# MineSwipper_Main_controller_USB.net
KiCad netlist of a schematic drawn in EAGLE
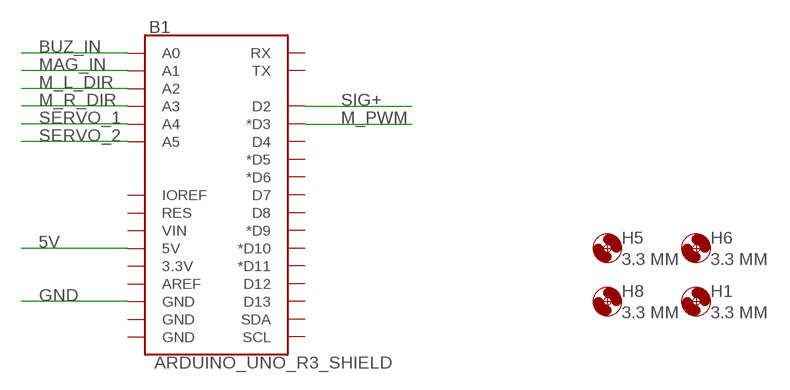
[diagram p0: schematic, sheet 1]
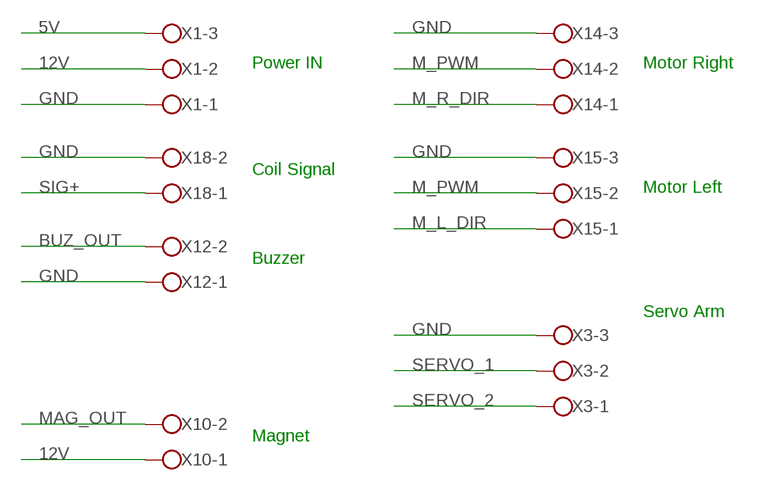
[diagram p1: schematic, sheet 2]
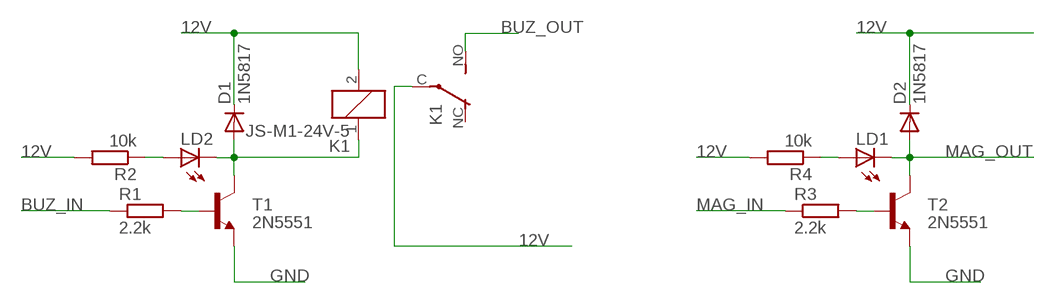
[diagram p2: schematic, sheet 3]

(export (version "E")
  (design (tool "Eeschema 10.0.6"))
  (components
    (comp (ref "D1")
      (value "1N5817")
      (footprint "eagle-import:DO41-10")
      (libsource (lib "eagle-import") (part "1N4004"))
    )
    (comp (ref "D2")
      (value "1N5817")
      (footprint "eagle-import:DO41-10")
      (libsource (lib "eagle-import") (part "1N4004"))
    )
    (comp (ref "K1")
      (value "JS-M1-24V-5")
      (footprint "eagle-import:JS-M")
      (fields (field (name "MF") "FARNELL") (field (name "MPN") "JSM1-12V-5"))
      (libsource (lib "eagle-import") (part "JS-M1-12V-5"))
    )
    (comp (ref "LD1")
      (value "LED5MM")
      (footprint "eagle-import:LED5MM")
      (libsource (lib "eagle-import") (part "LED5MM"))
    )
    (comp (ref "LD2")
      (value "LED5MM")
      (footprint "eagle-import:LED5MM")
      (libsource (lib "eagle-import") (part "LED5MM"))
    )
    (comp (ref "R1")
      (value "2.2k")
      (footprint "eagle-import:0207_10")
      (libsource (lib "eagle-import") (part "R-EU_0207/10"))
    )
    (comp (ref "R2")
      (value "10k")
      (footprint "eagle-import:0207_10")
      (libsource (lib "eagle-import") (part "R-EU_0207/10"))
    )
    (comp (ref "R3")
      (value "2.2k")
      (footprint "eagle-import:0207_10")
      (libsource (lib "eagle-import") (part "R-EU_0207/10"))
    )
    (comp (ref "R4")
      (value "10k")
      (footprint "eagle-import:0207_10")
      (libsource (lib "eagle-import") (part "R-EU_0207/10"))
    )
    (comp (ref "T1")
      (value "2N5551")
      (footprint "eagle-import:TO92-EBC-OVAL")
      (libsource (lib "eagle-import") (part "2N2222"))
    )
    (comp (ref "T2")
      (value "2N5551")
      (footprint "eagle-import:TO92-EBC-OVAL")
      (libsource (lib "eagle-import") (part "2N2222"))
    )
    (comp (ref "X1")
      (value "W237-103")
      (footprint "eagle-import:W237-103")
      (fields (field (name "MPN") "237-103"))
      (libsource (lib "eagle-import") (part "W237-103"))
    )
    (comp (ref "X3")
      (value "W237-103")
      (footprint "eagle-import:W237-103")
      (fields (field (name "MPN") "237-103"))
      (libsource (lib "eagle-import") (part "W237-103"))
    )
    (comp (ref "X10")
      (value "W237-102")
      (footprint "eagle-import:W237-102")
      (fields (field (name "MPN") "237-102"))
      (libsource (lib "eagle-import") (part "W237-102"))
    )
    (comp (ref "X12")
      (value "W237-102")
      (footprint "eagle-import:W237-102")
      (fields (field (name "MPN") "237-102"))
      (libsource (lib "eagle-import") (part "W237-102"))
    )
    (comp (ref "X14")
      (value "W237-103")
      (footprint "eagle-import:W237-103")
      (fields (field (name "MPN") "237-103"))
      (libsource (lib "eagle-import") (part "W237-103"))
    )
    (comp (ref "X15")
      (value "W237-103")
      (footprint "eagle-import:W237-103")
      (fields (field (name "MPN") "237-103"))
      (libsource (lib "eagle-import") (part "W237-103"))
    )
    (comp (ref "X18")
      (value "W237-102")
      (footprint "eagle-import:W237-102")
      (fields (field (name "MPN") "237-102"))
      (libsource (lib "eagle-import") (part "W237-102"))
    )
    (comp (ref "B1")
      (value "ARDUINO_UNO_R3_SHIELD")
      (footprint "eagle-import:UNO_R3_SHIELD_NOLABELS_LOCK")
      (libsource (lib "eagle-import") (part "ARDUINO_UNO_R3_SHIELDUNO_R3_SHIELD_NOLABELS_LOCK"))
    )
    (comp (ref "H1")
      (value "3.3 MM")
      (footprint "eagle-import:3,3")
      (libsource (lib "eagle-import") (part "MOUNT-HOLE3.3"))
    )
    (comp (ref "H5")
      (value "3.3 MM")
      (footprint "eagle-import:3,3")
      (libsource (lib "eagle-import") (part "MOUNT-HOLE3.3"))
    )
    (comp (ref "H6")
      (value "3.3 MM")
      (footprint "eagle-import:3,3")
      (libsource (lib "eagle-import") (part "MOUNT-HOLE3.3"))
    )
    (comp (ref "H8")
      (value "3.3 MM")
      (footprint "eagle-import:3,3")
      (libsource (lib "eagle-import") (part "MOUNT-HOLE3.3"))
    )
  )
  (nets
    (net (code "1") (name "5V") (class "Default")
      (node (ref "B1") (pin "5V") (pinfunction "5V_5V") (pintype "bidirectional"))
      (node (ref "X1") (pin "3") (pinfunction "KL_3") (pintype "passive"))
    )
    (net (code "2") (name "12V") (class "Default")
      (node (ref "D1") (pin "C") (pinfunction "C_C") (pintype "passive"))
      (node (ref "D2") (pin "C") (pinfunction "C_C") (pintype "passive"))
      (node (ref "K1") (pin "2") (pinfunction "2_2") (pintype "passive"))
      (node (ref "K1") (pin "C") (pinfunction "P_C") (pintype "passive"))
      (node (ref "R2") (pin "2") (pinfunction "2_2") (pintype "passive"))
      (node (ref "R4") (pin "2") (pinfunction "2_2") (pintype "passive"))
      (node (ref "X1") (pin "2") (pinfunction "KL_2") (pintype "passive"))
      (node (ref "X10") (pin "1") (pinfunction "KL_1") (pintype "passive"))
    )
    (net (code "3") (name "BUZ_IN") (class "Default")
      (node (ref "B1") (pin "A0") (pinfunction "A0_A0") (pintype "bidirectional"))
      (node (ref "R1") (pin "1") (pinfunction "1_1") (pintype "passive"))
    )
    (net (code "4") (name "BUZ_OUT") (class "Default")
      (node (ref "K1") (pin "NO") (pinfunction "S_NO") (pintype "passive"))
      (node (ref "X12") (pin "2") (pinfunction "KL_2") (pintype "passive"))
    )
    (net (code "5") (name "GND") (class "Default")
      (node (ref "B1") (pin "GND@2") (pinfunction "GND_GND@2") (pintype "bidirectional"))
      (node (ref "T1") (pin "E") (pinfunction "E_E") (pintype "passive"))
      (node (ref "T2") (pin "E") (pinfunction "E_E") (pintype "passive"))
      (node (ref "X1") (pin "1") (pinfunction "KL_1") (pintype "passive"))
      (node (ref "X12") (pin "1") (pinfunction "KL_1") (pintype "passive"))
      (node (ref "X14") (pin "3") (pinfunction "KL_3") (pintype "passive"))
      (node (ref "X15") (pin "3") (pinfunction "KL_3") (pintype "passive"))
      (node (ref "X18") (pin "2") (pinfunction "KL_2") (pintype "passive"))
      (node (ref "X3") (pin "3") (pinfunction "KL_3") (pintype "passive"))
    )
    (net (code "6") (name "MAG_IN") (class "Default")
      (node (ref "B1") (pin "A1") (pinfunction "A1_A1") (pintype "bidirectional"))
      (node (ref "R3") (pin "1") (pinfunction "1_1") (pintype "passive"))
    )
    (net (code "7") (name "MAG_OUT") (class "Default")
      (node (ref "D2") (pin "A") (pinfunction "A_A") (pintype "passive"))
      (node (ref "LD1") (pin "K") (pinfunction "C_K") (pintype "passive"))
      (node (ref "T2") (pin "C") (pinfunction "C_C") (pintype "passive"))
      (node (ref "X10") (pin "2") (pinfunction "KL_2") (pintype "passive"))
    )
    (net (code "8") (name "M_L_DIR") (class "Default")
      (node (ref "B1") (pin "A2") (pinfunction "A2_A2") (pintype "bidirectional"))
      (node (ref "X15") (pin "1") (pinfunction "KL_1") (pintype "passive"))
    )
    (net (code "9") (name "M_PWM") (class "Default")
      (node (ref "B1") (pin "D3") (pinfunction "*D3_D3") (pintype "bidirectional"))
      (node (ref "X14") (pin "2") (pinfunction "KL_2") (pintype "passive"))
      (node (ref "X15") (pin "2") (pinfunction "KL_2") (pintype "passive"))
    )
    (net (code "10") (name "M_R_DIR") (class "Default")
      (node (ref "B1") (pin "A3") (pinfunction "A3_A3") (pintype "bidirectional"))
      (node (ref "X14") (pin "1") (pinfunction "KL_1") (pintype "passive"))
    )
    (net (code "11") (name "Net-(LD1-PadA)") (class "Default")
      (node (ref "LD1") (pin "A") (pinfunction "A_A") (pintype "passive"))
      (node (ref "R4") (pin "1") (pinfunction "1_1") (pintype "passive"))
    )
    (net (code "12") (name "Net-(LD2-C)") (class "Default")
      (node (ref "D1") (pin "A") (pinfunction "A_A") (pintype "passive"))
      (node (ref "K1") (pin "1") (pinfunction "1_1") (pintype "passive"))
      (node (ref "LD2") (pin "K") (pinfunction "C_K") (pintype "passive"))
      (node (ref "T1") (pin "C") (pinfunction "C_C") (pintype "passive"))
    )
    (net (code "13") (name "Net-(LD2-PadA)") (class "Default")
      (node (ref "LD2") (pin "A") (pinfunction "A_A") (pintype "passive"))
      (node (ref "R2") (pin "1") (pinfunction "1_1") (pintype "passive"))
    )
    (net (code "14") (name "Net-(R1-Pad2)") (class "Default")
      (node (ref "R1") (pin "2") (pinfunction "2_2") (pintype "passive"))
      (node (ref "T1") (pin "B") (pinfunction "B_B") (pintype "passive"))
    )
    (net (code "15") (name "Net-(R3-Pad2)") (class "Default")
      (node (ref "R3") (pin "2") (pinfunction "2_2") (pintype "passive"))
      (node (ref "T2") (pin "B") (pinfunction "B_B") (pintype "passive"))
    )
    (net (code "16") (name "SERVO_1") (class "Default")
      (node (ref "B1") (pin "A4") (pinfunction "A4_A4") (pintype "bidirectional"))
      (node (ref "X3") (pin "2") (pinfunction "KL_2") (pintype "passive"))
    )
    (net (code "17") (name "SERVO_2") (class "Default")
      (node (ref "B1") (pin "A5") (pinfunction "A5_A5") (pintype "bidirectional"))
      (node (ref "X3") (pin "1") (pinfunction "KL_1") (pintype "passive"))
    )
    (net (code "18") (name "SIG+") (class "Default")
      (node (ref "B1") (pin "D2") (pinfunction "D2_D2") (pintype "bidirectional"))
      (node (ref "X18") (pin "1") (pinfunction "KL_1") (pintype "passive"))
    )
    (net (code "19") (name "unconnected-(B1-*D5-PadD5)") (class "Default")
      (node (ref "B1") (pin "D5") (pinfunction "*D5_D5") (pintype "bidirectional"))
    )
    (net (code "20") (name "unconnected-(B1-*D6-PadD6)") (class "Default")
      (node (ref "B1") (pin "D6") (pinfunction "*D6_D6") (pintype "bidirectional"))
    )
    (net (code "21") (name "unconnected-(B1-*D9-PadD9)") (class "Default")
      (node (ref "B1") (pin "D9") (pinfunction "*D9_D9") (pintype "bidirectional"))
    )
    (net (code "22") (name "unconnected-(B1-*D10-PadD10)") (class "Default")
      (node (ref "B1") (pin "D10") (pinfunction "*D10_D10") (pintype "bidirectional"))
    )
    (net (code "23") (name "unconnected-(B1-*D11-PadD11)") (class "Default")
      (node (ref "B1") (pin "D11") (pinfunction "*D11_D11") (pintype "bidirectional"))
    )
    (net (code "24") (name "unconnected-(B1-GND-PadGND@0)") (class "Default")
      (node (ref "B1") (pin "GND@0") (pinfunction "GND_GND@0") (pintype "bidirectional"))
    )
    (net (code "25") (name "unconnected-(B1-GND-PadGND@1)") (class "Default")
      (node (ref "B1") (pin "GND@1") (pinfunction "GND_GND@1") (pintype "bidirectional"))
    )
    (net (code "26") (name "unconnected-(B1-Pad3.3V)") (class "Default")
      (node (ref "B1") (pin "3.3V") (pinfunction "3.3V_3.3V") (pintype "bidirectional"))
    )
    (net (code "27") (name "unconnected-(B1-PadAREF)") (class "Default")
      (node (ref "B1") (pin "AREF") (pinfunction "AREF_AREF") (pintype "bidirectional"))
    )
    (net (code "28") (name "unconnected-(B1-PadD4)") (class "Default")
      (node (ref "B1") (pin "D4") (pinfunction "D4_D4") (pintype "bidirectional"))
    )
    (net (code "29") (name "unconnected-(B1-PadD7)") (class "Default")
      (node (ref "B1") (pin "D7") (pinfunction "D7_D7") (pintype "bidirectional"))
    )
    (net (code "30") (name "unconnected-(B1-PadD8)") (class "Default")
      (node (ref "B1") (pin "D8") (pinfunction "D8_D8") (pintype "bidirectional"))
    )
    (net (code "31") (name "unconnected-(B1-PadD12)") (class "Default")
      (node (ref "B1") (pin "D12") (pinfunction "D12_D12") (pintype "bidirectional"))
    )
    (net (code "32") (name "unconnected-(B1-PadD13)") (class "Default")
      (node (ref "B1") (pin "D13") (pinfunction "D13_D13") (pintype "bidirectional"))
    )
    (net (code "33") (name "unconnected-(B1-PadIOREF)") (class "Default")
      (node (ref "B1") (pin "IOREF") (pinfunction "IOREF_IOREF") (pintype "bidirectional"))
    )
    (net (code "34") (name "unconnected-(B1-PadRES)") (class "Default")
      (node (ref "B1") (pin "RES") (pinfunction "RES_RES") (pintype "bidirectional"))
    )
    (net (code "35") (name "unconnected-(B1-PadRX)") (class "Default")
      (node (ref "B1") (pin "RX") (pinfunction "RX_RX") (pintype "bidirectional"))
    )
    (net (code "36") (name "unconnected-(B1-PadSCL)") (class "Default")
      (node (ref "B1") (pin "SCL") (pinfunction "SCL_SCL") (pintype "bidirectional"))
    )
    (net (code "37") (name "unconnected-(B1-PadSDA)") (class "Default")
      (node (ref "B1") (pin "SDA") (pinfunction "SDA_SDA") (pintype "bidirectional"))
    )
    (net (code "38") (name "unconnected-(B1-PadTX)") (class "Default")
      (node (ref "B1") (pin "TX") (pinfunction "TX_TX") (pintype "bidirectional"))
    )
    (net (code "39") (name "unconnected-(B1-PadVIN)") (class "Default")
      (node (ref "B1") (pin "VIN") (pinfunction "VIN_VIN") (pintype "bidirectional"))
    )
    (net (code "40") (name "unconnected-(K1B-O-PadNC)") (class "Default")
      (node (ref "K1") (pin "NC") (pinfunction "O_NC") (pintype "passive"))
    )
  )
)
